# LED_Board_Schematic.net
KiCad netlist of a schematic drawn in Altium Designer
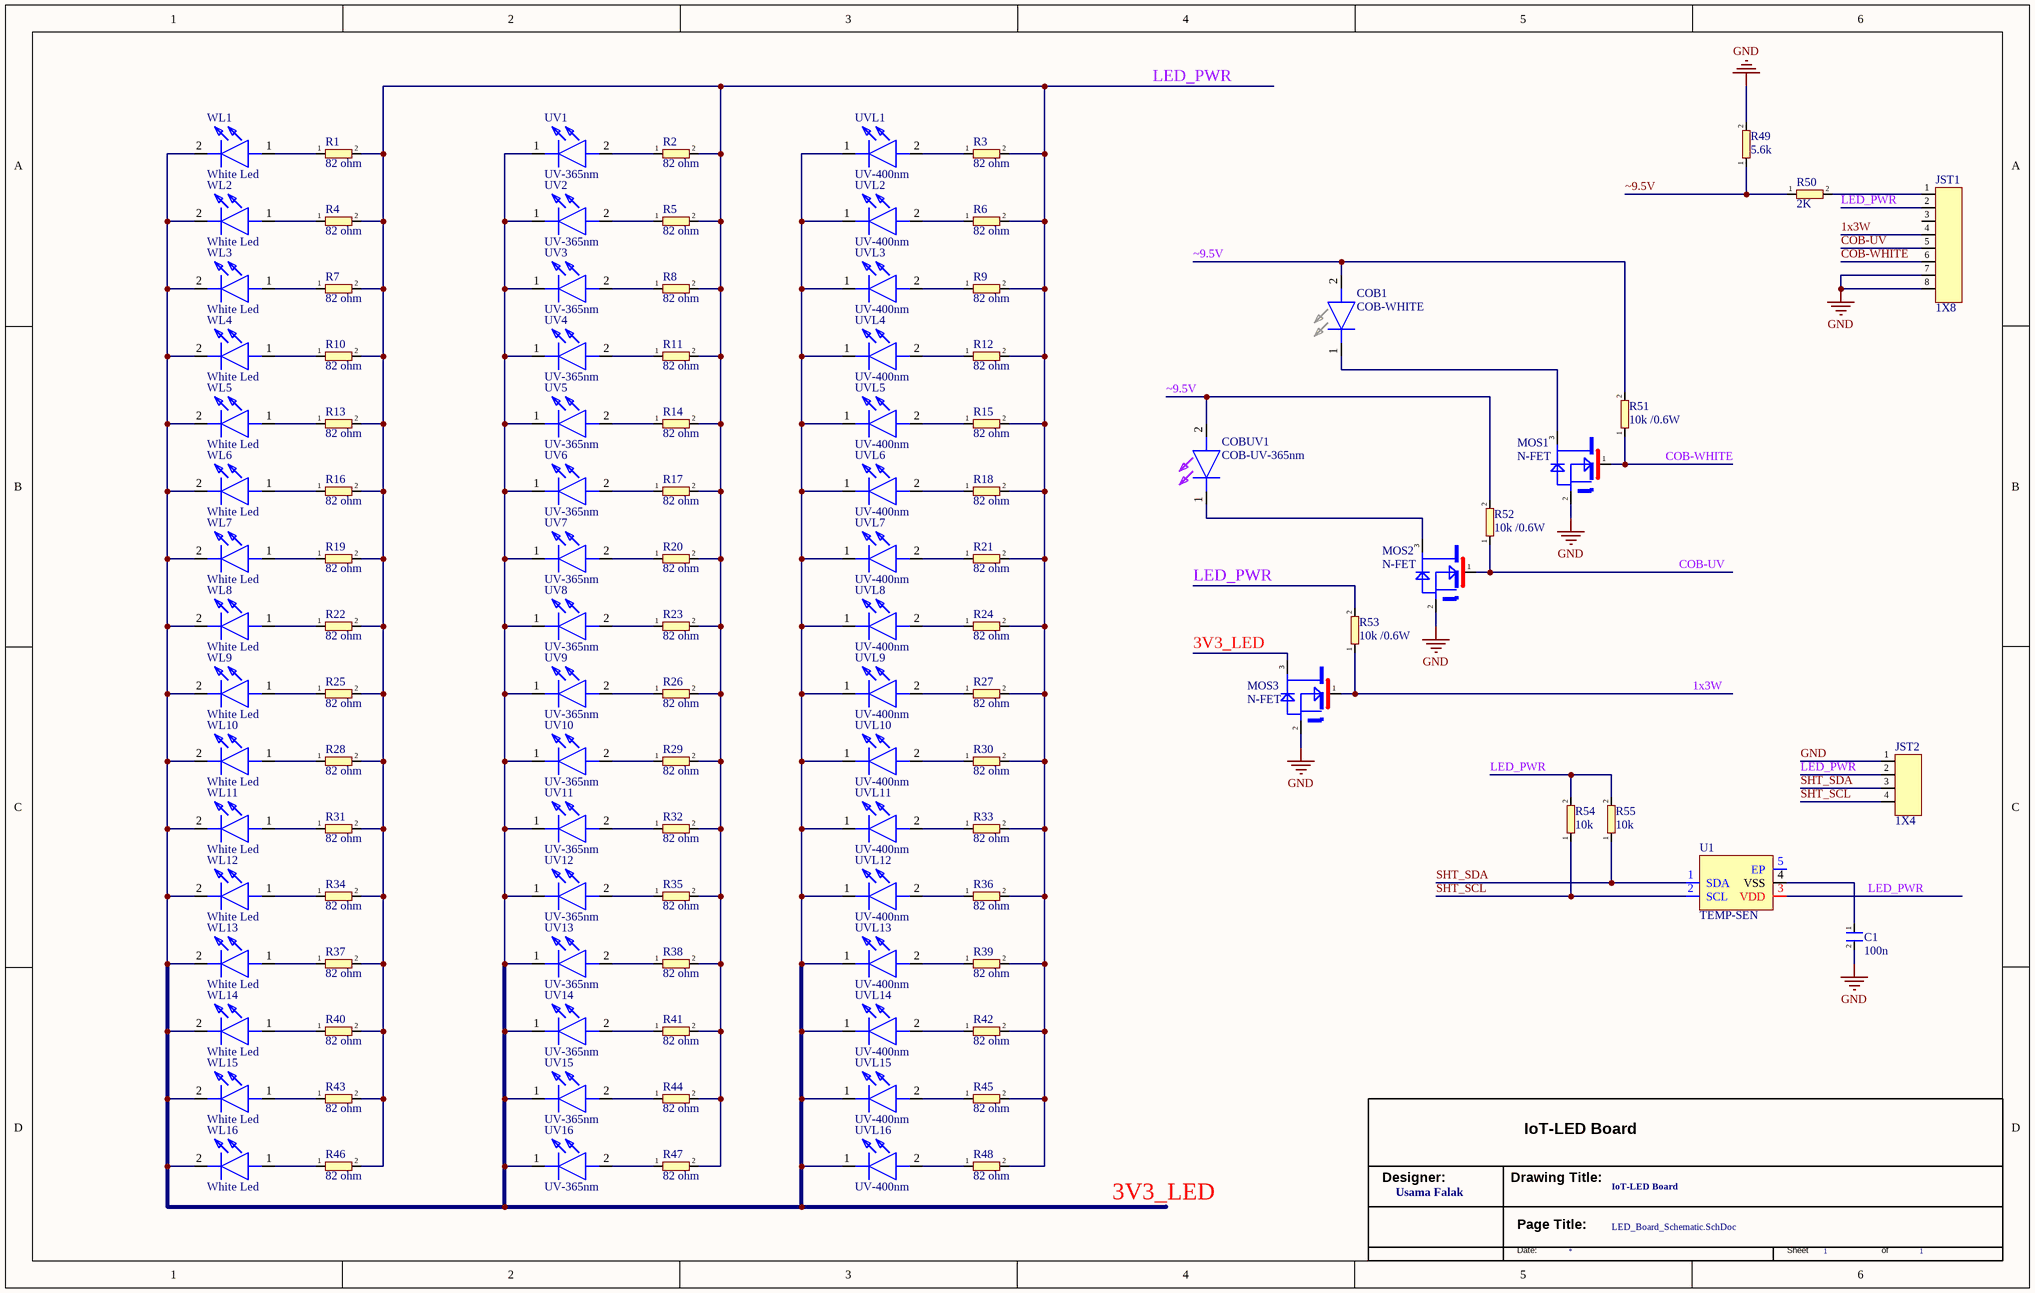
[diagram p0: LED_Board_Schematic.SchDoc]

(export (version "E")
  (design (tool "Eeschema 10.0.6"))
  (components
    (comp (ref "*") (value "TitleBlock_MCPG") (libsource (lib "LED_Board_SCHLIB") (part "TitleBlock_MCPG")))
    (comp (ref "C1")
      (value "100n")
      (footprint "SMD-C0603-CAP")
      (description "50V 100nF X7R ±10% 0603 Multilayer Ceramic Capacitors MLCC - SMD/SMT ROHS")
      (fields (field (name "LCSC-PART#") "C478888") (field (name "MANUFACTURER-PART#") "C0603B104K500NT"))
      (libsource (lib "LED_Board_SCHLIB") (part "SMD CAP 100n"))
    )
    (comp (ref "COB1")
      (value "COB-WHITE")
      (footprint "COB-LED")
      (fields (field (name "LCSC-PART#") "NONE") (field (name "MANUFACTURER-PART#") "‎1DGL-JC-10W-WH"))
      (libsource (lib "LED_Board_SCHLIB") (part "COB-WHITE"))
    )
    (comp (ref "COBUV1")
      (value "COB-UV-365nm")
      (footprint "COB-LED")
      (fields (field (name "LCSC-PART#") "NONE") (field (name "MANUFACTURER-PART#") "‎JH-10V14G45-R1C-370"))
      (libsource (lib "LED_Board_SCHLIB") (part "COB-365nm"))
    )
    (comp (ref "JST1")
      (value "1X8")
      (footprint "JST_1X8_Right Angle")
      (fields (field (name "LCSC-PART#") "C495701") (field (name "MANUFACTURER-PART#") "S08B-PASK-2(LF)(SN)"))
      (libsource (lib "LED_Board_SCHLIB") (part "JST 1x8_Right Angle"))
    )
    (comp (ref "JST2")
      (value "1X4")
      (footprint "JST_1X4_Right Angle")
      (fields (field (name "LCSC-PART#") "C265068") (field (name "MANUFACTURER-PART#") "S4B-EH(LF)(SN)"))
      (libsource (lib "LED_Board_SCHLIB") (part "JST 1x4_Right Angle"))
    )
    (comp (ref "MOS1")
      (value "N-FET")
      (footprint "SOT-23")
      (description "20V 6.3A 1.3W 21mΩ@4.5V,6.3A 1.1V 1 N-channel SOT-23 MOSFETs ROHS")
      (fields (field (name "LCSC-PART#") "C5364311") (field (name "MANUFACTURER-PART#") "IRLML6244"))
      (libsource (lib "LED_Board_SCHLIB") (part "N-Channel-MOSFET"))
    )
    (comp (ref "MOS2")
      (value "N-FET")
      (footprint "SOT-23")
      (description "20V 6.3A 1.3W 21mΩ@4.5V,6.3A 1.1V 1 N-channel SOT-23 MOSFETs ROHS")
      (fields (field (name "LCSC-PART#") "C5364311") (field (name "MANUFACTURER-PART#") "IRLML6244"))
      (libsource (lib "LED_Board_SCHLIB") (part "N-Channel-MOSFET"))
    )
    (comp (ref "MOS3")
      (value "N-FET")
      (footprint "SOT-23")
      (description "20V 6.3A 1.3W 21mΩ@4.5V,6.3A 1.1V 1 N-channel SOT-23 MOSFETs ROHS")
      (fields (field (name "LCSC-PART#") "C5364311") (field (name "MANUFACTURER-PART#") "IRLML6244"))
      (libsource (lib "LED_Board_SCHLIB") (part "N-Channel-MOSFET"))
    )
    (comp (ref "R1")
      (value "82 ohm")
      (footprint "SMD-1210-RES")
      (description "500mW Thick Film Resistors 200V ±100ppm/℃ ±1% 82Ω 1210 Chip Resistor - Surface Mount ROHS")
      (fields (field (name "LCSC-PART#") "C230357") (field (name "MANUFACTURER-PART#") "AC1210FR-0782RL"))
      (libsource (lib "LED_Board_SCHLIB") (part "SMD Resistor 82"))
    )
    (comp (ref "R2")
      (value "82 ohm")
      (footprint "SMD-1210-RES")
      (description "500mW Thick Film Resistors 200V ±100ppm/℃ ±1% 82Ω 1210 Chip Resistor - Surface Mount ROHS")
      (fields (field (name "LCSC-PART#") "C230357") (field (name "MANUFACTURER-PART#") "AC1210FR-0782RL"))
      (libsource (lib "LED_Board_SCHLIB") (part "SMD Resistor 82"))
    )
    (comp (ref "R3")
      (value "82 ohm")
      (footprint "SMD-1210-RES")
      (description "500mW Thick Film Resistors 200V ±100ppm/℃ ±1% 82Ω 1210 Chip Resistor - Surface Mount ROHS")
      (fields (field (name "LCSC-PART#") "C230357") (field (name "MANUFACTURER-PART#") "AC1210FR-0782RL"))
      (libsource (lib "LED_Board_SCHLIB") (part "SMD Resistor 82"))
    )
    (comp (ref "R4")
      (value "82 ohm")
      (footprint "SMD-1210-RES")
      (description "500mW Thick Film Resistors 200V ±100ppm/℃ ±1% 82Ω 1210 Chip Resistor - Surface Mount ROHS")
      (fields (field (name "LCSC-PART#") "C230357") (field (name "MANUFACTURER-PART#") "AC1210FR-0782RL"))
      (libsource (lib "LED_Board_SCHLIB") (part "SMD Resistor 82"))
    )
    (comp (ref "R5")
      (value "82 ohm")
      (footprint "SMD-1210-RES")
      (description "500mW Thick Film Resistors 200V ±100ppm/℃ ±1% 82Ω 1210 Chip Resistor - Surface Mount ROHS")
      (fields (field (name "LCSC-PART#") "C230357") (field (name "MANUFACTURER-PART#") "AC1210FR-0782RL"))
      (libsource (lib "LED_Board_SCHLIB") (part "SMD Resistor 82"))
    )
    (comp (ref "R6")
      (value "82 ohm")
      (footprint "SMD-1210-RES")
      (description "500mW Thick Film Resistors 200V ±100ppm/℃ ±1% 82Ω 1210 Chip Resistor - Surface Mount ROHS")
      (fields (field (name "LCSC-PART#") "C230357") (field (name "MANUFACTURER-PART#") "AC1210FR-0782RL"))
      (libsource (lib "LED_Board_SCHLIB") (part "SMD Resistor 82"))
    )
    (comp (ref "R7")
      (value "82 ohm")
      (footprint "SMD-1210-RES")
      (description "500mW Thick Film Resistors 200V ±100ppm/℃ ±1% 82Ω 1210 Chip Resistor - Surface Mount ROHS")
      (fields (field (name "LCSC-PART#") "C230357") (field (name "MANUFACTURER-PART#") "AC1210FR-0782RL"))
      (libsource (lib "LED_Board_SCHLIB") (part "SMD Resistor 82"))
    )
    (comp (ref "R8")
      (value "82 ohm")
      (footprint "SMD-1210-RES")
      (description "500mW Thick Film Resistors 200V ±100ppm/℃ ±1% 82Ω 1210 Chip Resistor - Surface Mount ROHS")
      (fields (field (name "LCSC-PART#") "C230357") (field (name "MANUFACTURER-PART#") "AC1210FR-0782RL"))
      (libsource (lib "LED_Board_SCHLIB") (part "SMD Resistor 82"))
    )
    (comp (ref "R9")
      (value "82 ohm")
      (footprint "SMD-1210-RES")
      (description "500mW Thick Film Resistors 200V ±100ppm/℃ ±1% 82Ω 1210 Chip Resistor - Surface Mount ROHS")
      (fields (field (name "LCSC-PART#") "C230357") (field (name "MANUFACTURER-PART#") "AC1210FR-0782RL"))
      (libsource (lib "LED_Board_SCHLIB") (part "SMD Resistor 82"))
    )
    (comp (ref "R10")
      (value "82 ohm")
      (footprint "SMD-1210-RES")
      (description "500mW Thick Film Resistors 200V ±100ppm/℃ ±1% 82Ω 1210 Chip Resistor - Surface Mount ROHS")
      (fields (field (name "LCSC-PART#") "C230357") (field (name "MANUFACTURER-PART#") "AC1210FR-0782RL"))
      (libsource (lib "LED_Board_SCHLIB") (part "SMD Resistor 82"))
    )
    (comp (ref "R11")
      (value "82 ohm")
      (footprint "SMD-1210-RES")
      (description "500mW Thick Film Resistors 200V ±100ppm/℃ ±1% 82Ω 1210 Chip Resistor - Surface Mount ROHS")
      (fields (field (name "LCSC-PART#") "C230357") (field (name "MANUFACTURER-PART#") "AC1210FR-0782RL"))
      (libsource (lib "LED_Board_SCHLIB") (part "SMD Resistor 82"))
    )
    (comp (ref "R12")
      (value "82 ohm")
      (footprint "SMD-1210-RES")
      (description "500mW Thick Film Resistors 200V ±100ppm/℃ ±1% 82Ω 1210 Chip Resistor - Surface Mount ROHS")
      (fields (field (name "LCSC-PART#") "C230357") (field (name "MANUFACTURER-PART#") "AC1210FR-0782RL"))
      (libsource (lib "LED_Board_SCHLIB") (part "SMD Resistor 82"))
    )
    (comp (ref "R13")
      (value "82 ohm")
      (footprint "SMD-1210-RES")
      (description "500mW Thick Film Resistors 200V ±100ppm/℃ ±1% 82Ω 1210 Chip Resistor - Surface Mount ROHS")
      (fields (field (name "LCSC-PART#") "C230357") (field (name "MANUFACTURER-PART#") "AC1210FR-0782RL"))
      (libsource (lib "LED_Board_SCHLIB") (part "SMD Resistor 82"))
    )
    (comp (ref "R14")
      (value "82 ohm")
      (footprint "SMD-1210-RES")
      (description "500mW Thick Film Resistors 200V ±100ppm/℃ ±1% 82Ω 1210 Chip Resistor - Surface Mount ROHS")
      (fields (field (name "LCSC-PART#") "C230357") (field (name "MANUFACTURER-PART#") "AC1210FR-0782RL"))
      (libsource (lib "LED_Board_SCHLIB") (part "SMD Resistor 82"))
    )
    (comp (ref "R15")
      (value "82 ohm")
      (footprint "SMD-1210-RES")
      (description "500mW Thick Film Resistors 200V ±100ppm/℃ ±1% 82Ω 1210 Chip Resistor - Surface Mount ROHS")
      (fields (field (name "LCSC-PART#") "C230357") (field (name "MANUFACTURER-PART#") "AC1210FR-0782RL"))
      (libsource (lib "LED_Board_SCHLIB") (part "SMD Resistor 82"))
    )
    (comp (ref "R16")
      (value "82 ohm")
      (footprint "SMD-1210-RES")
      (description "500mW Thick Film Resistors 200V ±100ppm/℃ ±1% 82Ω 1210 Chip Resistor - Surface Mount ROHS")
      (fields (field (name "LCSC-PART#") "C230357") (field (name "MANUFACTURER-PART#") "AC1210FR-0782RL"))
      (libsource (lib "LED_Board_SCHLIB") (part "SMD Resistor 82"))
    )
    (comp (ref "R17")
      (value "82 ohm")
      (footprint "SMD-1210-RES")
      (description "500mW Thick Film Resistors 200V ±100ppm/℃ ±1% 82Ω 1210 Chip Resistor - Surface Mount ROHS")
      (fields (field (name "LCSC-PART#") "C230357") (field (name "MANUFACTURER-PART#") "AC1210FR-0782RL"))
      (libsource (lib "LED_Board_SCHLIB") (part "SMD Resistor 82"))
    )
    (comp (ref "R18")
      (value "82 ohm")
      (footprint "SMD-1210-RES")
      (description "500mW Thick Film Resistors 200V ±100ppm/℃ ±1% 82Ω 1210 Chip Resistor - Surface Mount ROHS")
      (fields (field (name "LCSC-PART#") "C230357") (field (name "MANUFACTURER-PART#") "AC1210FR-0782RL"))
      (libsource (lib "LED_Board_SCHLIB") (part "SMD Resistor 82"))
    )
    (comp (ref "R19")
      (value "82 ohm")
      (footprint "SMD-1210-RES")
      (description "500mW Thick Film Resistors 200V ±100ppm/℃ ±1% 82Ω 1210 Chip Resistor - Surface Mount ROHS")
      (fields (field (name "LCSC-PART#") "C230357") (field (name "MANUFACTURER-PART#") "AC1210FR-0782RL"))
      (libsource (lib "LED_Board_SCHLIB") (part "SMD Resistor 82"))
    )
    (comp (ref "R20")
      (value "82 ohm")
      (footprint "SMD-1210-RES")
      (description "500mW Thick Film Resistors 200V ±100ppm/℃ ±1% 82Ω 1210 Chip Resistor - Surface Mount ROHS")
      (fields (field (name "LCSC-PART#") "C230357") (field (name "MANUFACTURER-PART#") "AC1210FR-0782RL"))
      (libsource (lib "LED_Board_SCHLIB") (part "SMD Resistor 82"))
    )
    (comp (ref "R21")
      (value "82 ohm")
      (footprint "SMD-1210-RES")
      (description "500mW Thick Film Resistors 200V ±100ppm/℃ ±1% 82Ω 1210 Chip Resistor - Surface Mount ROHS")
      (fields (field (name "LCSC-PART#") "C230357") (field (name "MANUFACTURER-PART#") "AC1210FR-0782RL"))
      (libsource (lib "LED_Board_SCHLIB") (part "SMD Resistor 82"))
    )
    (comp (ref "R22")
      (value "82 ohm")
      (footprint "SMD-1210-RES")
      (description "500mW Thick Film Resistors 200V ±100ppm/℃ ±1% 82Ω 1210 Chip Resistor - Surface Mount ROHS")
      (fields (field (name "LCSC-PART#") "C230357") (field (name "MANUFACTURER-PART#") "AC1210FR-0782RL"))
      (libsource (lib "LED_Board_SCHLIB") (part "SMD Resistor 82"))
    )
    (comp (ref "R23")
      (value "82 ohm")
      (footprint "SMD-1210-RES")
      (description "500mW Thick Film Resistors 200V ±100ppm/℃ ±1% 82Ω 1210 Chip Resistor - Surface Mount ROHS")
      (fields (field (name "LCSC-PART#") "C230357") (field (name "MANUFACTURER-PART#") "AC1210FR-0782RL"))
      (libsource (lib "LED_Board_SCHLIB") (part "SMD Resistor 82"))
    )
    (comp (ref "R24")
      (value "82 ohm")
      (footprint "SMD-1210-RES")
      (description "500mW Thick Film Resistors 200V ±100ppm/℃ ±1% 82Ω 1210 Chip Resistor - Surface Mount ROHS")
      (fields (field (name "LCSC-PART#") "C230357") (field (name "MANUFACTURER-PART#") "AC1210FR-0782RL"))
      (libsource (lib "LED_Board_SCHLIB") (part "SMD Resistor 82"))
    )
    (comp (ref "R25")
      (value "82 ohm")
      (footprint "SMD-1210-RES")
      (description "500mW Thick Film Resistors 200V ±100ppm/℃ ±1% 82Ω 1210 Chip Resistor - Surface Mount ROHS")
      (fields (field (name "LCSC-PART#") "C230357") (field (name "MANUFACTURER-PART#") "AC1210FR-0782RL"))
      (libsource (lib "LED_Board_SCHLIB") (part "SMD Resistor 82"))
    )
    (comp (ref "R26")
      (value "82 ohm")
      (footprint "SMD-1210-RES")
      (description "500mW Thick Film Resistors 200V ±100ppm/℃ ±1% 82Ω 1210 Chip Resistor - Surface Mount ROHS")
      (fields (field (name "LCSC-PART#") "C230357") (field (name "MANUFACTURER-PART#") "AC1210FR-0782RL"))
      (libsource (lib "LED_Board_SCHLIB") (part "SMD Resistor 82"))
    )
    (comp (ref "R27")
      (value "82 ohm")
      (footprint "SMD-1210-RES")
      (description "500mW Thick Film Resistors 200V ±100ppm/℃ ±1% 82Ω 1210 Chip Resistor - Surface Mount ROHS")
      (fields (field (name "LCSC-PART#") "C230357") (field (name "MANUFACTURER-PART#") "AC1210FR-0782RL"))
      (libsource (lib "LED_Board_SCHLIB") (part "SMD Resistor 82"))
    )
    (comp (ref "R28")
      (value "82 ohm")
      (footprint "SMD-1210-RES")
      (description "500mW Thick Film Resistors 200V ±100ppm/℃ ±1% 82Ω 1210 Chip Resistor - Surface Mount ROHS")
      (fields (field (name "LCSC-PART#") "C230357") (field (name "MANUFACTURER-PART#") "AC1210FR-0782RL"))
      (libsource (lib "LED_Board_SCHLIB") (part "SMD Resistor 82"))
    )
    (comp (ref "R29")
      (value "82 ohm")
      (footprint "SMD-1210-RES")
      (description "500mW Thick Film Resistors 200V ±100ppm/℃ ±1% 82Ω 1210 Chip Resistor - Surface Mount ROHS")
      (fields (field (name "LCSC-PART#") "C230357") (field (name "MANUFACTURER-PART#") "AC1210FR-0782RL"))
      (libsource (lib "LED_Board_SCHLIB") (part "SMD Resistor 82"))
    )
    (comp (ref "R30")
      (value "82 ohm")
      (footprint "SMD-1210-RES")
      (description "500mW Thick Film Resistors 200V ±100ppm/℃ ±1% 82Ω 1210 Chip Resistor - Surface Mount ROHS")
      (fields (field (name "LCSC-PART#") "C230357") (field (name "MANUFACTURER-PART#") "AC1210FR-0782RL"))
      (libsource (lib "LED_Board_SCHLIB") (part "SMD Resistor 82"))
    )
    (comp (ref "R31")
      (value "82 ohm")
      (footprint "SMD-1210-RES")
      (description "500mW Thick Film Resistors 200V ±100ppm/℃ ±1% 82Ω 1210 Chip Resistor - Surface Mount ROHS")
      (fields (field (name "LCSC-PART#") "C230357") (field (name "MANUFACTURER-PART#") "AC1210FR-0782RL"))
      (libsource (lib "LED_Board_SCHLIB") (part "SMD Resistor 82"))
    )
    (comp (ref "R32")
      (value "82 ohm")
      (footprint "SMD-1210-RES")
      (description "500mW Thick Film Resistors 200V ±100ppm/℃ ±1% 82Ω 1210 Chip Resistor - Surface Mount ROHS")
      (fields (field (name "LCSC-PART#") "C230357") (field (name "MANUFACTURER-PART#") "AC1210FR-0782RL"))
      (libsource (lib "LED_Board_SCHLIB") (part "SMD Resistor 82"))
    )
    (comp (ref "R33")
      (value "82 ohm")
      (footprint "SMD-1210-RES")
      (description "500mW Thick Film Resistors 200V ±100ppm/℃ ±1% 82Ω 1210 Chip Resistor - Surface Mount ROHS")
      (fields (field (name "LCSC-PART#") "C230357") (field (name "MANUFACTURER-PART#") "AC1210FR-0782RL"))
      (libsource (lib "LED_Board_SCHLIB") (part "SMD Resistor 82"))
    )
    (comp (ref "R34")
      (value "82 ohm")
      (footprint "SMD-1210-RES")
      (description "500mW Thick Film Resistors 200V ±100ppm/℃ ±1% 82Ω 1210 Chip Resistor - Surface Mount ROHS")
      (fields (field (name "LCSC-PART#") "C230357") (field (name "MANUFACTURER-PART#") "AC1210FR-0782RL"))
      (libsource (lib "LED_Board_SCHLIB") (part "SMD Resistor 82"))
    )
    (comp (ref "R35")
      (value "82 ohm")
      (footprint "SMD-1210-RES")
      (description "500mW Thick Film Resistors 200V ±100ppm/℃ ±1% 82Ω 1210 Chip Resistor - Surface Mount ROHS")
      (fields (field (name "LCSC-PART#") "C230357") (field (name "MANUFACTURER-PART#") "AC1210FR-0782RL"))
      (libsource (lib "LED_Board_SCHLIB") (part "SMD Resistor 82"))
    )
    (comp (ref "R36")
      (value "82 ohm")
      (footprint "SMD-1210-RES")
      (description "500mW Thick Film Resistors 200V ±100ppm/℃ ±1% 82Ω 1210 Chip Resistor - Surface Mount ROHS")
      (fields (field (name "LCSC-PART#") "C230357") (field (name "MANUFACTURER-PART#") "AC1210FR-0782RL"))
      (libsource (lib "LED_Board_SCHLIB") (part "SMD Resistor 82"))
    )
    (comp (ref "R37")
      (value "82 ohm")
      (footprint "SMD-1210-RES")
      (description "500mW Thick Film Resistors 200V ±100ppm/℃ ±1% 82Ω 1210 Chip Resistor - Surface Mount ROHS")
      (fields (field (name "LCSC-PART#") "C230357") (field (name "MANUFACTURER-PART#") "AC1210FR-0782RL"))
      (libsource (lib "LED_Board_SCHLIB") (part "SMD Resistor 82"))
    )
    (comp (ref "R38")
      (value "82 ohm")
      (footprint "SMD-1210-RES")
      (description "500mW Thick Film Resistors 200V ±100ppm/℃ ±1% 82Ω 1210 Chip Resistor - Surface Mount ROHS")
      (fields (field (name "LCSC-PART#") "C230357") (field (name "MANUFACTURER-PART#") "AC1210FR-0782RL"))
      (libsource (lib "LED_Board_SCHLIB") (part "SMD Resistor 82"))
    )
    (comp (ref "R39")
      (value "82 ohm")
      (footprint "SMD-1210-RES")
      (description "500mW Thick Film Resistors 200V ±100ppm/℃ ±1% 82Ω 1210 Chip Resistor - Surface Mount ROHS")
      (fields (field (name "LCSC-PART#") "C230357") (field (name "MANUFACTURER-PART#") "AC1210FR-0782RL"))
      (libsource (lib "LED_Board_SCHLIB") (part "SMD Resistor 82"))
    )
    (comp (ref "R40")
      (value "82 ohm")
      (footprint "SMD-1210-RES")
      (description "500mW Thick Film Resistors 200V ±100ppm/℃ ±1% 82Ω 1210 Chip Resistor - Surface Mount ROHS")
      (fields (field (name "LCSC-PART#") "C230357") (field (name "MANUFACTURER-PART#") "AC1210FR-0782RL"))
      (libsource (lib "LED_Board_SCHLIB") (part "SMD Resistor 82"))
    )
    (comp (ref "R41")
      (value "82 ohm")
      (footprint "SMD-1210-RES")
      (description "500mW Thick Film Resistors 200V ±100ppm/℃ ±1% 82Ω 1210 Chip Resistor - Surface Mount ROHS")
      (fields (field (name "LCSC-PART#") "C230357") (field (name "MANUFACTURER-PART#") "AC1210FR-0782RL"))
      (libsource (lib "LED_Board_SCHLIB") (part "SMD Resistor 82"))
    )
    (comp (ref "R42")
      (value "82 ohm")
      (footprint "SMD-1210-RES")
      (description "500mW Thick Film Resistors 200V ±100ppm/℃ ±1% 82Ω 1210 Chip Resistor - Surface Mount ROHS")
      (fields (field (name "LCSC-PART#") "C230357") (field (name "MANUFACTURER-PART#") "AC1210FR-0782RL"))
      (libsource (lib "LED_Board_SCHLIB") (part "SMD Resistor 82"))
    )
    (comp (ref "R43")
      (value "82 ohm")
      (footprint "SMD-1210-RES")
      (description "500mW Thick Film Resistors 200V ±100ppm/℃ ±1% 82Ω 1210 Chip Resistor - Surface Mount ROHS")
      (fields (field (name "LCSC-PART#") "C230357") (field (name "MANUFACTURER-PART#") "AC1210FR-0782RL"))
      (libsource (lib "LED_Board_SCHLIB") (part "SMD Resistor 82"))
    )
    (comp (ref "R44")
      (value "82 ohm")
      (footprint "SMD-1210-RES")
      (description "500mW Thick Film Resistors 200V ±100ppm/℃ ±1% 82Ω 1210 Chip Resistor - Surface Mount ROHS")
      (fields (field (name "LCSC-PART#") "C230357") (field (name "MANUFACTURER-PART#") "AC1210FR-0782RL"))
      (libsource (lib "LED_Board_SCHLIB") (part "SMD Resistor 82"))
    )
    (comp (ref "R45")
      (value "82 ohm")
      (footprint "SMD-1210-RES")
      (description "500mW Thick Film Resistors 200V ±100ppm/℃ ±1% 82Ω 1210 Chip Resistor - Surface Mount ROHS")
      (fields (field (name "LCSC-PART#") "C230357") (field (name "MANUFACTURER-PART#") "AC1210FR-0782RL"))
      (libsource (lib "LED_Board_SCHLIB") (part "SMD Resistor 82"))
    )
    (comp (ref "R46")
      (value "82 ohm")
      (footprint "SMD-1210-RES")
      (description "500mW Thick Film Resistors 200V ±100ppm/℃ ±1% 82Ω 1210 Chip Resistor - Surface Mount ROHS")
      (fields (field (name "LCSC-PART#") "C230357") (field (name "MANUFACTURER-PART#") "AC1210FR-0782RL"))
      (libsource (lib "LED_Board_SCHLIB") (part "SMD Resistor 82"))
    )
    (comp (ref "R47")
      (value "82 ohm")
      (footprint "SMD-1210-RES")
      (description "500mW Thick Film Resistors 200V ±100ppm/℃ ±1% 82Ω 1210 Chip Resistor - Surface Mount ROHS")
      (fields (field (name "LCSC-PART#") "C230357") (field (name "MANUFACTURER-PART#") "AC1210FR-0782RL"))
      (libsource (lib "LED_Board_SCHLIB") (part "SMD Resistor 82"))
    )
    (comp (ref "R48")
      (value "82 ohm")
      (footprint "SMD-1210-RES")
      (description "500mW Thick Film Resistors 200V ±100ppm/℃ ±1% 82Ω 1210 Chip Resistor - Surface Mount ROHS")
      (fields (field (name "LCSC-PART#") "C230357") (field (name "MANUFACTURER-PART#") "AC1210FR-0782RL"))
      (libsource (lib "LED_Board_SCHLIB") (part "SMD Resistor 82"))
    )
    (comp (ref "R49")
      (value "5.6k")
      (footprint "SMD-2010-RES")
      (description "0.75W Thick Film Resistors 200V ±100ppm/℃ ±1% 5.6kΩ 2010 Chip Resistor - Surface Mount ROHS")
      (fields (field (name "LCSC-PART#") "C407021") (field (name "MANUFACTURER-PART#") "201007F5601T4E"))
      (libsource (lib "LED_Board_SCHLIB") (part "SMD Resistor 5.6k"))
    )
    (comp (ref "R50")
      (value "2K")
      (footprint "SMD-2010-RES")
      (description "0.75W Thick Film Resistors 200V ±100ppm/℃ ±1% 2kΩ 2010 Chip Resistor - Surface Mount ROHS")
      (fields (field (name "LCSC-PART#") "C421898") (field (name "MANUFACTURER-PART#") "201007F2001T4E"))
      (libsource (lib "LED_Board_SCHLIB") (part "SMD Resistor 2K"))
    )
    (comp (ref "R51")
      (value "10k /0.6W")
      (footprint "SMD-1210-RES")
      (description "0.6W Thick Film Resistors 200V ±100ppm/℃ ±5% 2.2MΩ 1206 Chip Resistor - Surface Mount ROHS")
      (fields (field (name "LCSC-PART#") "C966067") (field (name "MANUFACTURER-PART#") "AS0606J0225T5E"))
      (libsource (lib "LED_Board_SCHLIB") (part "SMD Resistor 10K-1210"))
    )
    (comp (ref "R52")
      (value "10k /0.6W")
      (footprint "SMD-1210-RES")
      (description "0.6W Thick Film Resistors 200V ±100ppm/℃ ±5% 2.2MΩ 1206 Chip Resistor - Surface Mount ROHS")
      (fields (field (name "LCSC-PART#") "C966067") (field (name "MANUFACTURER-PART#") "AS0606J0225T5E"))
      (libsource (lib "LED_Board_SCHLIB") (part "SMD Resistor 10K-1210"))
    )
    (comp (ref "R53")
      (value "10k /0.6W")
      (footprint "SMD-1210-RES")
      (description "0.6W Thick Film Resistors 200V ±100ppm/℃ ±5% 2.2MΩ 1206 Chip Resistor - Surface Mount ROHS")
      (fields (field (name "LCSC-PART#") "C966067") (field (name "MANUFACTURER-PART#") "AS0606J0225T5E"))
      (libsource (lib "LED_Board_SCHLIB") (part "SMD Resistor 10K-1210"))
    )
    (comp (ref "R54")
      (value "10k")
      (footprint "SMD-0603-RES")
      (description "0.1W Thin Film Resistor 75V ±0.1% ±25ppm/℃ 10kΩ 0603 Chip Resistor - Surface Mount ROHS")
      (fields (field (name "LCSC-PART#") "C190610") (field (name "MANUFACTURER-PART#") "ERA3AEB103V"))
      (libsource (lib "LED_Board_SCHLIB") (part "SMD Resistor 10k"))
    )
    (comp (ref "R55")
      (value "10k")
      (footprint "SMD-0603-RES")
      (description "0.1W Thin Film Resistor 75V ±0.1% ±25ppm/℃ 10kΩ 0603 Chip Resistor - Surface Mount ROHS")
      (fields (field (name "LCSC-PART#") "C190610") (field (name "MANUFACTURER-PART#") "ERA3AEB103V"))
      (libsource (lib "LED_Board_SCHLIB") (part "SMD Resistor 10k"))
    )
    (comp (ref "U1")
      (value "TEMP-SEN")
      (footprint "SHT-41-TEMP-SENSOR")
      (fields (field (name "LCSC-PART#") "C7461862") (field (name "MANUFACTURER-PART#") "SHT41-AD1F-R2"))
      (libsource (lib "LED_Board_SCHLIB") (part "SHT-41"))
    )
    (comp (ref "UV1")
      (value "UV-365nm")
      (footprint "SMD-2835-UV365NM")
      (fields
        (field (name "LCSC-PART#") "C7500131")
        (field (name "MANUFACTURER-PART#") "JNJ-LTHU0106W30/Q15mil/365-370NM")
      )
      (libsource (lib "LED_Board_SCHLIB") (part "UV365nm"))
    )
    (comp (ref "UV2")
      (value "UV-365nm")
      (footprint "SMD-2835-UV365NM")
      (fields
        (field (name "LCSC-PART#") "C7500131")
        (field (name "MANUFACTURER-PART#") "JNJ-LTHU0106W30/Q15mil/365-370NM")
      )
      (libsource (lib "LED_Board_SCHLIB") (part "UV365nm"))
    )
    (comp (ref "UV3")
      (value "UV-365nm")
      (footprint "SMD-2835-UV365NM")
      (fields
        (field (name "LCSC-PART#") "C7500131")
        (field (name "MANUFACTURER-PART#") "JNJ-LTHU0106W30/Q15mil/365-370NM")
      )
      (libsource (lib "LED_Board_SCHLIB") (part "UV365nm"))
    )
    (comp (ref "UV4")
      (value "UV-365nm")
      (footprint "SMD-2835-UV365NM")
      (fields
        (field (name "LCSC-PART#") "C7500131")
        (field (name "MANUFACTURER-PART#") "JNJ-LTHU0106W30/Q15mil/365-370NM")
      )
      (libsource (lib "LED_Board_SCHLIB") (part "UV365nm"))
    )
    (comp (ref "UV5")
      (value "UV-365nm")
      (footprint "SMD-2835-UV365NM")
      (fields
        (field (name "LCSC-PART#") "C7500131")
        (field (name "MANUFACTURER-PART#") "JNJ-LTHU0106W30/Q15mil/365-370NM")
      )
      (libsource (lib "LED_Board_SCHLIB") (part "UV365nm"))
    )
    (comp (ref "UV6")
      (value "UV-365nm")
      (footprint "SMD-2835-UV365NM")
      (fields
        (field (name "LCSC-PART#") "C7500131")
        (field (name "MANUFACTURER-PART#") "JNJ-LTHU0106W30/Q15mil/365-370NM")
      )
      (libsource (lib "LED_Board_SCHLIB") (part "UV365nm"))
    )
    (comp (ref "UV7")
      (value "UV-365nm")
      (footprint "SMD-2835-UV365NM")
      (fields
        (field (name "LCSC-PART#") "C7500131")
        (field (name "MANUFACTURER-PART#") "JNJ-LTHU0106W30/Q15mil/365-370NM")
      )
      (libsource (lib "LED_Board_SCHLIB") (part "UV365nm"))
    )
    (comp (ref "UV8")
      (value "UV-365nm")
      (footprint "SMD-2835-UV365NM")
      (fields
        (field (name "LCSC-PART#") "C7500131")
        (field (name "MANUFACTURER-PART#") "JNJ-LTHU0106W30/Q15mil/365-370NM")
      )
      (libsource (lib "LED_Board_SCHLIB") (part "UV365nm"))
    )
    (comp (ref "UV9")
      (value "UV-365nm")
      (footprint "SMD-2835-UV365NM")
      (fields
        (field (name "LCSC-PART#") "C7500131")
        (field (name "MANUFACTURER-PART#") "JNJ-LTHU0106W30/Q15mil/365-370NM")
      )
      (libsource (lib "LED_Board_SCHLIB") (part "UV365nm"))
    )
    (comp (ref "UV10")
      (value "UV-365nm")
      (footprint "SMD-2835-UV365NM")
      (fields
        (field (name "LCSC-PART#") "C7500131")
        (field (name "MANUFACTURER-PART#") "JNJ-LTHU0106W30/Q15mil/365-370NM")
      )
      (libsource (lib "LED_Board_SCHLIB") (part "UV365nm"))
    )
    (comp (ref "UV11")
      (value "UV-365nm")
      (footprint "SMD-2835-UV365NM")
      (fields
        (field (name "LCSC-PART#") "C7500131")
        (field (name "MANUFACTURER-PART#") "JNJ-LTHU0106W30/Q15mil/365-370NM")
      )
      (libsource (lib "LED_Board_SCHLIB") (part "UV365nm"))
    )
    (comp (ref "UV12")
      (value "UV-365nm")
      (footprint "SMD-2835-UV365NM")
      (fields
        (field (name "LCSC-PART#") "C7500131")
        (field (name "MANUFACTURER-PART#") "JNJ-LTHU0106W30/Q15mil/365-370NM")
      )
      (libsource (lib "LED_Board_SCHLIB") (part "UV365nm"))
    )
    (comp (ref "UV13")
      (value "UV-365nm")
      (footprint "SMD-2835-UV365NM")
      (fields
        (field (name "LCSC-PART#") "C7500131")
        (field (name "MANUFACTURER-PART#") "JNJ-LTHU0106W30/Q15mil/365-370NM")
      )
      (libsource (lib "LED_Board_SCHLIB") (part "UV365nm"))
    )
    (comp (ref "UV14")
      (value "UV-365nm")
      (footprint "SMD-2835-UV365NM")
      (fields
        (field (name "LCSC-PART#") "C7500131")
        (field (name "MANUFACTURER-PART#") "JNJ-LTHU0106W30/Q15mil/365-370NM")
      )
      (libsource (lib "LED_Board_SCHLIB") (part "UV365nm"))
    )
    (comp (ref "UV15")
      (value "UV-365nm")
      (footprint "SMD-2835-UV365NM")
      (fields
        (field (name "LCSC-PART#") "C7500131")
        (field (name "MANUFACTURER-PART#") "JNJ-LTHU0106W30/Q15mil/365-370NM")
      )
      (libsource (lib "LED_Board_SCHLIB") (part "UV365nm"))
    )
    (comp (ref "UV16")
      (value "UV-365nm")
      (footprint "SMD-2835-UV365NM")
      (fields
        (field (name "LCSC-PART#") "C7500131")
        (field (name "MANUFACTURER-PART#") "JNJ-LTHU0106W30/Q15mil/365-370NM")
      )
      (libsource (lib "LED_Board_SCHLIB") (part "UV365nm"))
    )
    (comp (ref "UVL1")
      (value "UV-400nm")
      (footprint "SMD-2835-UV400NM")
      (fields
        (field (name "LCSC-PART#") "C7500135")
        (field (name "MANUFACTURER-PART#") "JNJ-LTHU0108W60/Q20mil/400-405NM")
      )
      (libsource (lib "LED_Board_SCHLIB") (part "UV400nm"))
    )
    (comp (ref "UVL2")
      (value "UV-400nm")
      (footprint "SMD-2835-UV400NM")
      (fields
        (field (name "LCSC-PART#") "C7500135")
        (field (name "MANUFACTURER-PART#") "JNJ-LTHU0108W60/Q20mil/400-405NM")
      )
      (libsource (lib "LED_Board_SCHLIB") (part "UV400nm"))
    )
    (comp (ref "UVL3")
      (value "UV-400nm")
      (footprint "SMD-2835-UV400NM")
      (fields
        (field (name "LCSC-PART#") "C7500135")
        (field (name "MANUFACTURER-PART#") "JNJ-LTHU0108W60/Q20mil/400-405NM")
      )
      (libsource (lib "LED_Board_SCHLIB") (part "UV400nm"))
    )
    (comp (ref "UVL4")
      (value "UV-400nm")
      (footprint "SMD-2835-UV400NM")
      (fields
        (field (name "LCSC-PART#") "C7500135")
        (field (name "MANUFACTURER-PART#") "JNJ-LTHU0108W60/Q20mil/400-405NM")
      )
      (libsource (lib "LED_Board_SCHLIB") (part "UV400nm"))
    )
    (comp (ref "UVL5")
      (value "UV-400nm")
      (footprint "SMD-2835-UV400NM")
      (fields
        (field (name "LCSC-PART#") "C7500135")
        (field (name "MANUFACTURER-PART#") "JNJ-LTHU0108W60/Q20mil/400-405NM")
      )
      (libsource (lib "LED_Board_SCHLIB") (part "UV400nm"))
    )
    (comp (ref "UVL6")
      (value "UV-400nm")
      (footprint "SMD-2835-UV400NM")
      (fields
        (field (name "LCSC-PART#") "C7500135")
        (field (name "MANUFACTURER-PART#") "JNJ-LTHU0108W60/Q20mil/400-405NM")
      )
      (libsource (lib "LED_Board_SCHLIB") (part "UV400nm"))
    )
    (comp (ref "UVL7")
      (value "UV-400nm")
      (footprint "SMD-2835-UV400NM")
      (fields
        (field (name "LCSC-PART#") "C7500135")
        (field (name "MANUFACTURER-PART#") "JNJ-LTHU0108W60/Q20mil/400-405NM")
      )
      (libsource (lib "LED_Board_SCHLIB") (part "UV400nm"))
    )
    (comp (ref "UVL8")
      (value "UV-400nm")
      (footprint "SMD-2835-UV400NM")
      (fields
        (field (name "LCSC-PART#") "C7500135")
        (field (name "MANUFACTURER-PART#") "JNJ-LTHU0108W60/Q20mil/400-405NM")
      )
      (libsource (lib "LED_Board_SCHLIB") (part "UV400nm"))
    )
    (comp (ref "UVL9")
      (value "UV-400nm")
      (footprint "SMD-2835-UV400NM")
      (fields
        (field (name "LCSC-PART#") "C7500135")
        (field (name "MANUFACTURER-PART#") "JNJ-LTHU0108W60/Q20mil/400-405NM")
      )
      (libsource (lib "LED_Board_SCHLIB") (part "UV400nm"))
    )
    (comp (ref "UVL10")
      (value "UV-400nm")
      (footprint "SMD-2835-UV400NM")
      (fields
        (field (name "LCSC-PART#") "C7500135")
        (field (name "MANUFACTURER-PART#") "JNJ-LTHU0108W60/Q20mil/400-405NM")
      )
      (libsource (lib "LED_Board_SCHLIB") (part "UV400nm"))
    )
    (comp (ref "UVL11")
      (value "UV-400nm")
      (footprint "SMD-2835-UV400NM")
      (fields
        (field (name "LCSC-PART#") "C7500135")
        (field (name "MANUFACTURER-PART#") "JNJ-LTHU0108W60/Q20mil/400-405NM")
      )
      (libsource (lib "LED_Board_SCHLIB") (part "UV400nm"))
    )
    (comp (ref "UVL12")
      (value "UV-400nm")
      (footprint "SMD-2835-UV400NM")
      (fields
        (field (name "LCSC-PART#") "C7500135")
        (field (name "MANUFACTURER-PART#") "JNJ-LTHU0108W60/Q20mil/400-405NM")
      )
      (libsource (lib "LED_Board_SCHLIB") (part "UV400nm"))
    )
    (comp (ref "UVL13")
      (value "UV-400nm")
      (footprint "SMD-2835-UV400NM")
      (fields
        (field (name "LCSC-PART#") "C7500135")
        (field (name "MANUFACTURER-PART#") "JNJ-LTHU0108W60/Q20mil/400-405NM")
      )
      (libsource (lib "LED_Board_SCHLIB") (part "UV400nm"))
    )
    (comp (ref "UVL14")
      (value "UV-400nm")
      (footprint "SMD-2835-UV400NM")
      (fields
        (field (name "LCSC-PART#") "C7500135")
        (field (name "MANUFACTURER-PART#") "JNJ-LTHU0108W60/Q20mil/400-405NM")
      )
      (libsource (lib "LED_Board_SCHLIB") (part "UV400nm"))
    )
    (comp (ref "UVL15")
      (value "UV-400nm")
      (footprint "SMD-2835-UV400NM")
      (fields
        (field (name "LCSC-PART#") "C7500135")
        (field (name "MANUFACTURER-PART#") "JNJ-LTHU0108W60/Q20mil/400-405NM")
      )
      (libsource (lib "LED_Board_SCHLIB") (part "UV400nm"))
    )
    (comp (ref "UVL16")
      (value "UV-400nm")
      (footprint "SMD-2835-UV400NM")
      (fields
        (field (name "LCSC-PART#") "C7500135")
        (field (name "MANUFACTURER-PART#") "JNJ-LTHU0108W60/Q20mil/400-405NM")
      )
      (libsource (lib "LED_Board_SCHLIB") (part "UV400nm"))
    )
    (comp (ref "WL1")
      (value "White Led")
      (footprint "SMD-2835-WHITE")
      (description "150mA 5500K~6500K 48000mcd -40℃~+100℃ White 60° 3V~3.6V SMD2835 LED Indication - Discrete ROHS")
      (fields
        (field (name "LCSC-PART#") "C7500119")
        (field (name "MANUFACTURER-PART#") "JNJ-LTJH0102W60/9x26mil/5500-6500K")
      )
      (libsource (lib "LED_Board_SCHLIB") (part "White"))
    )
    (comp (ref "WL2")
      (value "White Led")
      (footprint "SMD-2835-WHITE")
      (description "150mA 5500K~6500K 48000mcd -40℃~+100℃ White 60° 3V~3.6V SMD2835 LED Indication - Discrete ROHS")
      (fields
        (field (name "LCSC-PART#") "C7500119")
        (field (name "MANUFACTURER-PART#") "JNJ-LTJH0102W60/9x26mil/5500-6500K")
      )
      (libsource (lib "LED_Board_SCHLIB") (part "White"))
    )
    (comp (ref "WL3")
      (value "White Led")
      (footprint "SMD-2835-WHITE")
      (description "150mA 5500K~6500K 48000mcd -40℃~+100℃ White 60° 3V~3.6V SMD2835 LED Indication - Discrete ROHS")
      (fields
        (field (name "LCSC-PART#") "C7500119")
        (field (name "MANUFACTURER-PART#") "JNJ-LTJH0102W60/9x26mil/5500-6500K")
      )
      (libsource (lib "LED_Board_SCHLIB") (part "White"))
    )
    (comp (ref "WL4")
      (value "White Led")
      (footprint "SMD-2835-WHITE")
      (description "150mA 5500K~6500K 48000mcd -40℃~+100℃ White 60° 3V~3.6V SMD2835 LED Indication - Discrete ROHS")
      (fields
        (field (name "LCSC-PART#") "C7500119")
        (field (name "MANUFACTURER-PART#") "JNJ-LTJH0102W60/9x26mil/5500-6500K")
      )
      (libsource (lib "LED_Board_SCHLIB") (part "White"))
    )
    (comp (ref "WL5")
      (value "White Led")
      (footprint "SMD-2835-WHITE")
      (description "150mA 5500K~6500K 48000mcd -40℃~+100℃ White 60° 3V~3.6V SMD2835 LED Indication - Discrete ROHS")
      (fields
        (field (name "LCSC-PART#") "C7500119")
        (field (name "MANUFACTURER-PART#") "JNJ-LTJH0102W60/9x26mil/5500-6500K")
      )
      (libsource (lib "LED_Board_SCHLIB") (part "White"))
    )
    (comp (ref "WL6")
      (value "White Led")
      (footprint "SMD-2835-WHITE")
      (description "150mA 5500K~6500K 48000mcd -40℃~+100℃ White 60° 3V~3.6V SMD2835 LED Indication - Discrete ROHS")
      (fields
        (field (name "LCSC-PART#") "C7500119")
        (field (name "MANUFACTURER-PART#") "JNJ-LTJH0102W60/9x26mil/5500-6500K")
      )
      (libsource (lib "LED_Board_SCHLIB") (part "White"))
    )
    (comp (ref "WL7")
      (value "White Led")
      (footprint "SMD-2835-WHITE")
      (description "150mA 5500K~6500K 48000mcd -40℃~+100℃ White 60° 3V~3.6V SMD2835 LED Indication - Discrete ROHS")
      (fields
        (field (name "LCSC-PART#") "C7500119")
        (field (name "MANUFACTURER-PART#") "JNJ-LTJH0102W60/9x26mil/5500-6500K")
      )
      (libsource (lib "LED_Board_SCHLIB") (part "White"))
    )
    (comp (ref "WL8")
      (value "White Led")
      (footprint "SMD-2835-WHITE")
      (description "150mA 5500K~6500K 48000mcd -40℃~+100℃ White 60° 3V~3.6V SMD2835 LED Indication - Discrete ROHS")
      (fields
        (field (name "LCSC-PART#") "C7500119")
        (field (name "MANUFACTURER-PART#") "JNJ-LTJH0102W60/9x26mil/5500-6500K")
      )
      (libsource (lib "LED_Board_SCHLIB") (part "White"))
    )
    (comp (ref "WL9")
      (value "White Led")
      (footprint "SMD-2835-WHITE")
      (description "150mA 5500K~6500K 48000mcd -40℃~+100℃ White 60° 3V~3.6V SMD2835 LED Indication - Discrete ROHS")
      (fields
        (field (name "LCSC-PART#") "C7500119")
        (field (name "MANUFACTURER-PART#") "JNJ-LTJH0102W60/9x26mil/5500-6500K")
      )
      (libsource (lib "LED_Board_SCHLIB") (part "White"))
    )
    (comp (ref "WL10")
      (value "White Led")
      (footprint "SMD-2835-WHITE")
      (description "150mA 5500K~6500K 48000mcd -40℃~+100℃ White 60° 3V~3.6V SMD2835 LED Indication - Discrete ROHS")
      (fields
        (field (name "LCSC-PART#") "C7500119")
        (field (name "MANUFACTURER-PART#") "JNJ-LTJH0102W60/9x26mil/5500-6500K")
      )
      (libsource (lib "LED_Board_SCHLIB") (part "White"))
    )
    (comp (ref "WL11")
      (value "White Led")
      (footprint "SMD-2835-WHITE")
      (description "150mA 5500K~6500K 48000mcd -40℃~+100℃ White 60° 3V~3.6V SMD2835 LED Indication - Discrete ROHS")
      (fields
        (field (name "LCSC-PART#") "C7500119")
        (field (name "MANUFACTURER-PART#") "JNJ-LTJH0102W60/9x26mil/5500-6500K")
      )
      (libsource (lib "LED_Board_SCHLIB") (part "White"))
    )
    (comp (ref "WL12")
      (value "White Led")
      (footprint "SMD-2835-WHITE")
      (description "150mA 5500K~6500K 48000mcd -40℃~+100℃ White 60° 3V~3.6V SMD2835 LED Indication - Discrete ROHS")
      (fields
        (field (name "LCSC-PART#") "C7500119")
        (field (name "MANUFACTURER-PART#") "JNJ-LTJH0102W60/9x26mil/5500-6500K")
      )
      (libsource (lib "LED_Board_SCHLIB") (part "White"))
    )
    (comp (ref "WL13")
      (value "White Led")
      (footprint "SMD-2835-WHITE")
      (description "150mA 5500K~6500K 48000mcd -40℃~+100℃ White 60° 3V~3.6V SMD2835 LED Indication - Discrete ROHS")
      (fields
        (field (name "LCSC-PART#") "C7500119")
        (field (name "MANUFACTURER-PART#") "JNJ-LTJH0102W60/9x26mil/5500-6500K")
      )
      (libsource (lib "LED_Board_SCHLIB") (part "White"))
    )
    (comp (ref "WL14")
      (value "White Led")
      (footprint "SMD-2835-WHITE")
      (description "150mA 5500K~6500K 48000mcd -40℃~+100℃ White 60° 3V~3.6V SMD2835 LED Indication - Discrete ROHS")
      (fields
        (field (name "LCSC-PART#") "C7500119")
        (field (name "MANUFACTURER-PART#") "JNJ-LTJH0102W60/9x26mil/5500-6500K")
      )
      (libsource (lib "LED_Board_SCHLIB") (part "White"))
    )
    (comp (ref "WL15")
      (value "White Led")
      (footprint "SMD-2835-WHITE")
      (description "150mA 5500K~6500K 48000mcd -40℃~+100℃ White 60° 3V~3.6V SMD2835 LED Indication - Discrete ROHS")
      (fields
        (field (name "LCSC-PART#") "C7500119")
        (field (name "MANUFACTURER-PART#") "JNJ-LTJH0102W60/9x26mil/5500-6500K")
      )
      (libsource (lib "LED_Board_SCHLIB") (part "White"))
    )
    (comp (ref "WL16")
      (value "White Led")
      (footprint "SMD-2835-WHITE")
      (description "150mA 5500K~6500K 48000mcd -40℃~+100℃ White 60° 3V~3.6V SMD2835 LED Indication - Discrete ROHS")
      (fields
        (field (name "LCSC-PART#") "C7500119")
        (field (name "MANUFACTURER-PART#") "JNJ-LTJH0102W60/9x26mil/5500-6500K")
      )
      (libsource (lib "LED_Board_SCHLIB") (part "White"))
    )
  )
  (nets
    (net (code "1") (name "/1x3W") (class "Default")
      (node (ref "JST1") (pin "4") (pintype "passive"))
      (node (ref "MOS3") (pin "1") (pinfunction "G_1") (pintype "passive"))
      (node (ref "R53") (pin "1") (pintype "passive"))
    )
    (net (code "2") (name "/3V3_LED") (class "Default")
      (node (ref "MOS3") (pin "3") (pinfunction "3_3") (pintype "passive"))
      (node (ref "UV1") (pin "1") (pinfunction "K_1") (pintype "passive"))
      (node (ref "UV10") (pin "1") (pinfunction "K_1") (pintype "passive"))
      (node (ref "UV11") (pin "1") (pinfunction "K_1") (pintype "passive"))
      (node (ref "UV12") (pin "1") (pinfunction "K_1") (pintype "passive"))
      (node (ref "UV13") (pin "1") (pinfunction "K_1") (pintype "passive"))
      (node (ref "UV14") (pin "1") (pinfunction "K_1") (pintype "passive"))
      (node (ref "UV15") (pin "1") (pinfunction "K_1") (pintype "passive"))
      (node (ref "UV16") (pin "1") (pinfunction "K_1") (pintype "passive"))
      (node (ref "UV2") (pin "1") (pinfunction "K_1") (pintype "passive"))
      (node (ref "UV3") (pin "1") (pinfunction "K_1") (pintype "passive"))
      (node (ref "UV4") (pin "1") (pinfunction "K_1") (pintype "passive"))
      (node (ref "UV5") (pin "1") (pinfunction "K_1") (pintype "passive"))
      (node (ref "UV6") (pin "1") (pinfunction "K_1") (pintype "passive"))
      (node (ref "UV7") (pin "1") (pinfunction "K_1") (pintype "passive"))
      (node (ref "UV8") (pin "1") (pinfunction "K_1") (pintype "passive"))
      (node (ref "UV9") (pin "1") (pinfunction "K_1") (pintype "passive"))
      (node (ref "UVL1") (pin "1") (pinfunction "K_1") (pintype "passive"))
      (node (ref "UVL10") (pin "1") (pinfunction "K_1") (pintype "passive"))
      (node (ref "UVL11") (pin "1") (pinfunction "K_1") (pintype "passive"))
      (node (ref "UVL12") (pin "1") (pinfunction "K_1") (pintype "passive"))
      (node (ref "UVL13") (pin "1") (pinfunction "K_1") (pintype "passive"))
      (node (ref "UVL14") (pin "1") (pinfunction "K_1") (pintype "passive"))
      (node (ref "UVL15") (pin "1") (pinfunction "K_1") (pintype "passive"))
      (node (ref "UVL16") (pin "1") (pinfunction "K_1") (pintype "passive"))
      (node (ref "UVL2") (pin "1") (pinfunction "K_1") (pintype "passive"))
      (node (ref "UVL3") (pin "1") (pinfunction "K_1") (pintype "passive"))
      (node (ref "UVL4") (pin "1") (pinfunction "K_1") (pintype "passive"))
      (node (ref "UVL5") (pin "1") (pinfunction "K_1") (pintype "passive"))
      (node (ref "UVL6") (pin "1") (pinfunction "K_1") (pintype "passive"))
      (node (ref "UVL7") (pin "1") (pinfunction "K_1") (pintype "passive"))
      (node (ref "UVL8") (pin "1") (pinfunction "K_1") (pintype "passive"))
      (node (ref "UVL9") (pin "1") (pinfunction "K_1") (pintype "passive"))
      (node (ref "WL1") (pin "2") (pinfunction "K_2") (pintype "passive"))
      (node (ref "WL10") (pin "2") (pinfunction "K_2") (pintype "passive"))
      (node (ref "WL11") (pin "2") (pinfunction "K_2") (pintype "passive"))
      (node (ref "WL12") (pin "2") (pinfunction "K_2") (pintype "passive"))
      (node (ref "WL13") (pin "2") (pinfunction "K_2") (pintype "passive"))
      (node (ref "WL14") (pin "2") (pinfunction "K_2") (pintype "passive"))
      (node (ref "WL15") (pin "2") (pinfunction "K_2") (pintype "passive"))
      (node (ref "WL16") (pin "2") (pinfunction "K_2") (pintype "passive"))
      (node (ref "WL2") (pin "2") (pinfunction "K_2") (pintype "passive"))
      (node (ref "WL3") (pin "2") (pinfunction "K_2") (pintype "passive"))
      (node (ref "WL4") (pin "2") (pinfunction "K_2") (pintype "passive"))
      (node (ref "WL5") (pin "2") (pinfunction "K_2") (pintype "passive"))
      (node (ref "WL6") (pin "2") (pinfunction "K_2") (pintype "passive"))
      (node (ref "WL7") (pin "2") (pinfunction "K_2") (pintype "passive"))
      (node (ref "WL8") (pin "2") (pinfunction "K_2") (pintype "passive"))
      (node (ref "WL9") (pin "2") (pinfunction "K_2") (pintype "passive"))
    )
    (net (code "3") (name "/COB-UV") (class "Default")
      (node (ref "JST1") (pin "5") (pinfunction "5_5") (pintype "passive"))
      (node (ref "MOS2") (pin "1") (pinfunction "G_1") (pintype "passive"))
      (node (ref "R52") (pin "1") (pintype "passive"))
    )
    (net (code "4") (name "/COB-WHITE") (class "Default")
      (node (ref "JST1") (pin "6") (pinfunction "6_6") (pintype "passive"))
      (node (ref "MOS1") (pin "1") (pinfunction "G_1") (pintype "passive"))
      (node (ref "R51") (pin "1") (pintype "passive"))
    )
    (net (code "5") (name "/LED_PWR") (class "Default")
      (node (ref "JST1") (pin "2") (pintype "passive"))
      (node (ref "JST2") (pin "2") (pintype "passive"))
      (node (ref "R1") (pin "2") (pintype "passive"))
      (node (ref "R10") (pin "2") (pintype "passive"))
      (node (ref "R11") (pin "2") (pintype "passive"))
      (node (ref "R12") (pin "2") (pintype "passive"))
      (node (ref "R13") (pin "2") (pintype "passive"))
      (node (ref "R14") (pin "2") (pintype "passive"))
      (node (ref "R15") (pin "2") (pintype "passive"))
      (node (ref "R16") (pin "2") (pintype "passive"))
      (node (ref "R17") (pin "2") (pintype "passive"))
      (node (ref "R18") (pin "2") (pintype "passive"))
      (node (ref "R19") (pin "2") (pintype "passive"))
      (node (ref "R2") (pin "2") (pintype "passive"))
      (node (ref "R20") (pin "2") (pintype "passive"))
      (node (ref "R21") (pin "2") (pintype "passive"))
      (node (ref "R22") (pin "2") (pintype "passive"))
      (node (ref "R23") (pin "2") (pintype "passive"))
      (node (ref "R24") (pin "2") (pintype "passive"))
      (node (ref "R25") (pin "2") (pintype "passive"))
      (node (ref "R26") (pin "2") (pintype "passive"))
      (node (ref "R27") (pin "2") (pintype "passive"))
      (node (ref "R28") (pin "2") (pintype "passive"))
      (node (ref "R29") (pin "2") (pintype "passive"))
      (node (ref "R3") (pin "2") (pintype "passive"))
      (node (ref "R30") (pin "2") (pintype "passive"))
      (node (ref "R31") (pin "2") (pintype "passive"))
      (node (ref "R32") (pin "2") (pintype "passive"))
      (node (ref "R33") (pin "2") (pintype "passive"))
      (node (ref "R34") (pin "2") (pintype "passive"))
      (node (ref "R35") (pin "2") (pintype "passive"))
      (node (ref "R36") (pin "2") (pintype "passive"))
      (node (ref "R37") (pin "2") (pintype "passive"))
      (node (ref "R38") (pin "2") (pintype "passive"))
      (node (ref "R39") (pin "2") (pintype "passive"))
      (node (ref "R4") (pin "2") (pintype "passive"))
      (node (ref "R40") (pin "2") (pintype "passive"))
      (node (ref "R41") (pin "2") (pintype "passive"))
      (node (ref "R42") (pin "2") (pintype "passive"))
      (node (ref "R43") (pin "2") (pintype "passive"))
      (node (ref "R44") (pin "2") (pintype "passive"))
      (node (ref "R45") (pin "2") (pintype "passive"))
      (node (ref "R46") (pin "2") (pintype "passive"))
      (node (ref "R47") (pin "2") (pintype "passive"))
      (node (ref "R48") (pin "2") (pintype "passive"))
      (node (ref "R5") (pin "2") (pintype "passive"))
      (node (ref "R53") (pin "2") (pintype "passive"))
      (node (ref "R54") (pin "2") (pintype "passive"))
      (node (ref "R55") (pin "2") (pintype "passive"))
      (node (ref "R6") (pin "2") (pintype "passive"))
      (node (ref "R7") (pin "2") (pintype "passive"))
      (node (ref "R8") (pin "2") (pintype "passive"))
      (node (ref "R9") (pin "2") (pintype "passive"))
      (node (ref "U1") (pin "3") (pinfunction "VDD_3") (pintype "passive"))
    )
    (net (code "6") (name "/SHT_SCL") (class "Default")
      (node (ref "JST2") (pin "4") (pintype "passive"))
      (node (ref "R54") (pin "1") (pintype "passive"))
      (node (ref "U1") (pin "2") (pinfunction "SCL_2") (pintype "passive"))
    )
    (net (code "7") (name "/SHT_SDA") (class "Default")
      (node (ref "JST2") (pin "3") (pintype "passive"))
      (node (ref "R55") (pin "1") (pintype "passive"))
      (node (ref "U1") (pin "1") (pinfunction "SDA_1") (pintype "passive"))
    )
    (net (code "8") (name "/~9.5V") (class "Default")
      (node (ref "COB1") (pin "2") (pinfunction "A_2") (pintype "passive"))
      (node (ref "COBUV1") (pin "2") (pinfunction "A_2") (pintype "passive"))
      (node (ref "R49") (pin "1") (pintype "passive"))
      (node (ref "R50") (pin "1") (pintype "passive"))
      (node (ref "R51") (pin "2") (pintype "passive"))
      (node (ref "R52") (pin "2") (pintype "passive"))
    )
    (net (code "9") (name "GND") (class "Default")
      (node (ref "C1") (pin "2") (pintype "passive"))
      (node (ref "JST1") (pin "7") (pinfunction "7_7") (pintype "passive"))
      (node (ref "JST1") (pin "8") (pinfunction "8_8") (pintype "passive"))
      (node (ref "JST2") (pin "1") (pintype "passive"))
      (node (ref "MOS1") (pin "2") (pinfunction "2_2") (pintype "passive"))
      (node (ref "MOS2") (pin "2") (pinfunction "2_2") (pintype "passive"))
      (node (ref "MOS3") (pin "2") (pinfunction "2_2") (pintype "passive"))
      (node (ref "R49") (pin "2") (pintype "passive"))
    )
    (net (code "10") (name "Net-(COB1-K)") (class "Default")
      (node (ref "COB1") (pin "1") (pinfunction "K_1") (pintype "passive"))
      (node (ref "MOS1") (pin "3") (pinfunction "3_3") (pintype "passive"))
    )
    (net (code "11") (name "Net-(COBUV1-K)") (class "Default")
      (node (ref "COBUV1") (pin "1") (pinfunction "K_1") (pintype "passive"))
      (node (ref "MOS2") (pin "3") (pinfunction "3_3") (pintype "passive"))
    )
    (net (code "12") (name "Net-(JST1-Pad1)") (class "Default")
      (node (ref "JST1") (pin "1") (pintype "passive"))
      (node (ref "R50") (pin "2") (pintype "passive"))
    )
    (net (code "13") (name "Net-(U1-VSS)") (class "Default")
      (node (ref "C1") (pin "1") (pintype "passive"))
      (node (ref "U1") (pin "4") (pinfunction "VSS_4") (pintype "passive"))
    )
    (net (code "14") (name "Net-(UV1-A)") (class "Default")
      (node (ref "R2") (pin "1") (pintype "passive"))
      (node (ref "UV1") (pin "2") (pinfunction "A_2") (pintype "passive"))
    )
    (net (code "15") (name "Net-(UV2-A)") (class "Default")
      (node (ref "R5") (pin "1") (pintype "passive"))
      (node (ref "UV2") (pin "2") (pinfunction "A_2") (pintype "passive"))
    )
    (net (code "16") (name "Net-(UV3-A)") (class "Default")
      (node (ref "R8") (pin "1") (pintype "passive"))
      (node (ref "UV3") (pin "2") (pinfunction "A_2") (pintype "passive"))
    )
    (net (code "17") (name "Net-(UV4-A)") (class "Default")
      (node (ref "R11") (pin "1") (pintype "passive"))
      (node (ref "UV4") (pin "2") (pinfunction "A_2") (pintype "passive"))
    )
    (net (code "18") (name "Net-(UV5-A)") (class "Default")
      (node (ref "R14") (pin "1") (pintype "passive"))
      (node (ref "UV5") (pin "2") (pinfunction "A_2") (pintype "passive"))
    )
    (net (code "19") (name "Net-(UV6-A)") (class "Default")
      (node (ref "R17") (pin "1") (pintype "passive"))
      (node (ref "UV6") (pin "2") (pinfunction "A_2") (pintype "passive"))
    )
    (net (code "20") (name "Net-(UV7-A)") (class "Default")
      (node (ref "R20") (pin "1") (pintype "passive"))
      (node (ref "UV7") (pin "2") (pinfunction "A_2") (pintype "passive"))
    )
    (net (code "21") (name "Net-(UV8-A)") (class "Default")
      (node (ref "R23") (pin "1") (pintype "passive"))
      (node (ref "UV8") (pin "2") (pinfunction "A_2") (pintype "passive"))
    )
    (net (code "22") (name "Net-(UV9-A)") (class "Default")
      (node (ref "R26") (pin "1") (pintype "passive"))
      (node (ref "UV9") (pin "2") (pinfunction "A_2") (pintype "passive"))
    )
    (net (code "23") (name "Net-(UV10-A)") (class "Default")
      (node (ref "R29") (pin "1") (pintype "passive"))
      (node (ref "UV10") (pin "2") (pinfunction "A_2") (pintype "passive"))
    )
    (net (code "24") (name "Net-(UV11-A)") (class "Default")
      (node (ref "R32") (pin "1") (pintype "passive"))
      (node (ref "UV11") (pin "2") (pinfunction "A_2") (pintype "passive"))
    )
    (net (code "25") (name "Net-(UV12-A)") (class "Default")
      (node (ref "R35") (pin "1") (pintype "passive"))
      (node (ref "UV12") (pin "2") (pinfunction "A_2") (pintype "passive"))
    )
    (net (code "26") (name "Net-(UV13-A)") (class "Default")
      (node (ref "R38") (pin "1") (pintype "passive"))
      (node (ref "UV13") (pin "2") (pinfunction "A_2") (pintype "passive"))
    )
    (net (code "27") (name "Net-(UV14-A)") (class "Default")
      (node (ref "R41") (pin "1") (pintype "passive"))
      (node (ref "UV14") (pin "2") (pinfunction "A_2") (pintype "passive"))
    )
    (net (code "28") (name "Net-(UV15-A)") (class "Default")
      (node (ref "R44") (pin "1") (pintype "passive"))
      (node (ref "UV15") (pin "2") (pinfunction "A_2") (pintype "passive"))
    )
    (net (code "29") (name "Net-(UV16-A)") (class "Default")
      (node (ref "R47") (pin "1") (pintype "passive"))
      (node (ref "UV16") (pin "2") (pinfunction "A_2") (pintype "passive"))
    )
    (net (code "30") (name "Net-(UVL1-A)") (class "Default")
      (node (ref "R3") (pin "1") (pintype "passive"))
      (node (ref "UVL1") (pin "2") (pinfunction "A_2") (pintype "passive"))
    )
    (net (code "31") (name "Net-(UVL2-A)") (class "Default")
      (node (ref "R6") (pin "1") (pintype "passive"))
      (node (ref "UVL2") (pin "2") (pinfunction "A_2") (pintype "passive"))
    )
    (net (code "32") (name "Net-(UVL3-A)") (class "Default")
      (node (ref "R9") (pin "1") (pintype "passive"))
      (node (ref "UVL3") (pin "2") (pinfunction "A_2") (pintype "passive"))
    )
    (net (code "33") (name "Net-(UVL4-A)") (class "Default")
      (node (ref "R12") (pin "1") (pintype "passive"))
      (node (ref "UVL4") (pin "2") (pinfunction "A_2") (pintype "passive"))
    )
    (net (code "34") (name "Net-(UVL5-A)") (class "Default")
      (node (ref "R15") (pin "1") (pintype "passive"))
      (node (ref "UVL5") (pin "2") (pinfunction "A_2") (pintype "passive"))
    )
    (net (code "35") (name "Net-(UVL6-A)") (class "Default")
      (node (ref "R18") (pin "1") (pintype "passive"))
      (node (ref "UVL6") (pin "2") (pinfunction "A_2") (pintype "passive"))
    )
    (net (code "36") (name "Net-(UVL7-A)") (class "Default")
      (node (ref "R21") (pin "1") (pintype "passive"))
      (node (ref "UVL7") (pin "2") (pinfunction "A_2") (pintype "passive"))
    )
    (net (code "37") (name "Net-(UVL8-A)") (class "Default")
      (node (ref "R24") (pin "1") (pintype "passive"))
      (node (ref "UVL8") (pin "2") (pinfunction "A_2") (pintype "passive"))
    )
    (net (code "38") (name "Net-(UVL9-A)") (class "Default")
      (node (ref "R27") (pin "1") (pintype "passive"))
      (node (ref "UVL9") (pin "2") (pinfunction "A_2") (pintype "passive"))
    )
    (net (code "39") (name "Net-(UVL10-A)") (class "Default")
      (node (ref "R30") (pin "1") (pintype "passive"))
      (node (ref "UVL10") (pin "2") (pinfunction "A_2") (pintype "passive"))
    )
    (net (code "40") (name "Net-(UVL11-A)") (class "Default")
      (node (ref "R33") (pin "1") (pintype "passive"))
      (node (ref "UVL11") (pin "2") (pinfunction "A_2") (pintype "passive"))
    )
    (net (code "41") (name "Net-(UVL12-A)") (class "Default")
      (node (ref "R36") (pin "1") (pintype "passive"))
      (node (ref "UVL12") (pin "2") (pinfunction "A_2") (pintype "passive"))
    )
    (net (code "42") (name "Net-(UVL13-A)") (class "Default")
      (node (ref "R39") (pin "1") (pintype "passive"))
      (node (ref "UVL13") (pin "2") (pinfunction "A_2") (pintype "passive"))
    )
    (net (code "43") (name "Net-(UVL14-A)") (class "Default")
      (node (ref "R42") (pin "1") (pintype "passive"))
      (node (ref "UVL14") (pin "2") (pinfunction "A_2") (pintype "passive"))
    )
    (net (code "44") (name "Net-(UVL15-A)") (class "Default")
      (node (ref "R45") (pin "1") (pintype "passive"))
      (node (ref "UVL15") (pin "2") (pinfunction "A_2") (pintype "passive"))
    )
    (net (code "45") (name "Net-(UVL16-A)") (class "Default")
      (node (ref "R48") (pin "1") (pintype "passive"))
      (node (ref "UVL16") (pin "2") (pinfunction "A_2") (pintype "passive"))
    )
    (net (code "46") (name "Net-(WL1-A)") (class "Default")
      (node (ref "R1") (pin "1") (pintype "passive"))
      (node (ref "WL1") (pin "1") (pinfunction "A_1") (pintype "passive"))
    )
    (net (code "47") (name "Net-(WL2-A)") (class "Default")
      (node (ref "R4") (pin "1") (pintype "passive"))
      (node (ref "WL2") (pin "1") (pinfunction "A_1") (pintype "passive"))
    )
    (net (code "48") (name "Net-(WL3-A)") (class "Default")
      (node (ref "R7") (pin "1") (pintype "passive"))
      (node (ref "WL3") (pin "1") (pinfunction "A_1") (pintype "passive"))
    )
    (net (code "49") (name "Net-(WL4-A)") (class "Default")
      (node (ref "R10") (pin "1") (pintype "passive"))
      (node (ref "WL4") (pin "1") (pinfunction "A_1") (pintype "passive"))
    )
    (net (code "50") (name "Net-(WL5-A)") (class "Default")
      (node (ref "R13") (pin "1") (pintype "passive"))
      (node (ref "WL5") (pin "1") (pinfunction "A_1") (pintype "passive"))
    )
    (net (code "51") (name "Net-(WL6-A)") (class "Default")
      (node (ref "R16") (pin "1") (pintype "passive"))
      (node (ref "WL6") (pin "1") (pinfunction "A_1") (pintype "passive"))
    )
    (net (code "52") (name "Net-(WL7-A)") (class "Default")
      (node (ref "R19") (pin "1") (pintype "passive"))
      (node (ref "WL7") (pin "1") (pinfunction "A_1") (pintype "passive"))
    )
    (net (code "53") (name "Net-(WL8-A)") (class "Default")
      (node (ref "R22") (pin "1") (pintype "passive"))
      (node (ref "WL8") (pin "1") (pinfunction "A_1") (pintype "passive"))
    )
    (net (code "54") (name "Net-(WL9-A)") (class "Default")
      (node (ref "R25") (pin "1") (pintype "passive"))
      (node (ref "WL9") (pin "1") (pinfunction "A_1") (pintype "passive"))
    )
    (net (code "55") (name "Net-(WL10-A)") (class "Default")
      (node (ref "R28") (pin "1") (pintype "passive"))
      (node (ref "WL10") (pin "1") (pinfunction "A_1") (pintype "passive"))
    )
    (net (code "56") (name "Net-(WL11-A)") (class "Default")
      (node (ref "R31") (pin "1") (pintype "passive"))
      (node (ref "WL11") (pin "1") (pinfunction "A_1") (pintype "passive"))
    )
    (net (code "57") (name "Net-(WL12-A)") (class "Default")
      (node (ref "R34") (pin "1") (pintype "passive"))
      (node (ref "WL12") (pin "1") (pinfunction "A_1") (pintype "passive"))
    )
    (net (code "58") (name "Net-(WL13-A)") (class "Default")
      (node (ref "R37") (pin "1") (pintype "passive"))
      (node (ref "WL13") (pin "1") (pinfunction "A_1") (pintype "passive"))
    )
    (net (code "59") (name "Net-(WL14-A)") (class "Default")
      (node (ref "R40") (pin "1") (pintype "passive"))
      (node (ref "WL14") (pin "1") (pinfunction "A_1") (pintype "passive"))
    )
    (net (code "60") (name "Net-(WL15-A)") (class "Default")
      (node (ref "R43") (pin "1") (pintype "passive"))
      (node (ref "WL15") (pin "1") (pinfunction "A_1") (pintype "passive"))
    )
    (net (code "61") (name "Net-(WL16-A)") (class "Default")
      (node (ref "R46") (pin "1") (pintype "passive"))
      (node (ref "WL16") (pin "1") (pinfunction "A_1") (pintype "passive"))
    )
    (net (code "62") (name "unconnected-(JST1-Pad3)") (class "Default")
      (node (ref "JST1") (pin "3") (pintype "passive"))
    )
    (net (code "63") (name "unconnected-(U1-EP-Pad5)") (class "Default")
      (node (ref "U1") (pin "5") (pinfunction "EP_5") (pintype "passive"))
    )
  )
)
